# L1211_TOP_V2_0.net
KiCad netlist of a schematic drawn in Altium Designer
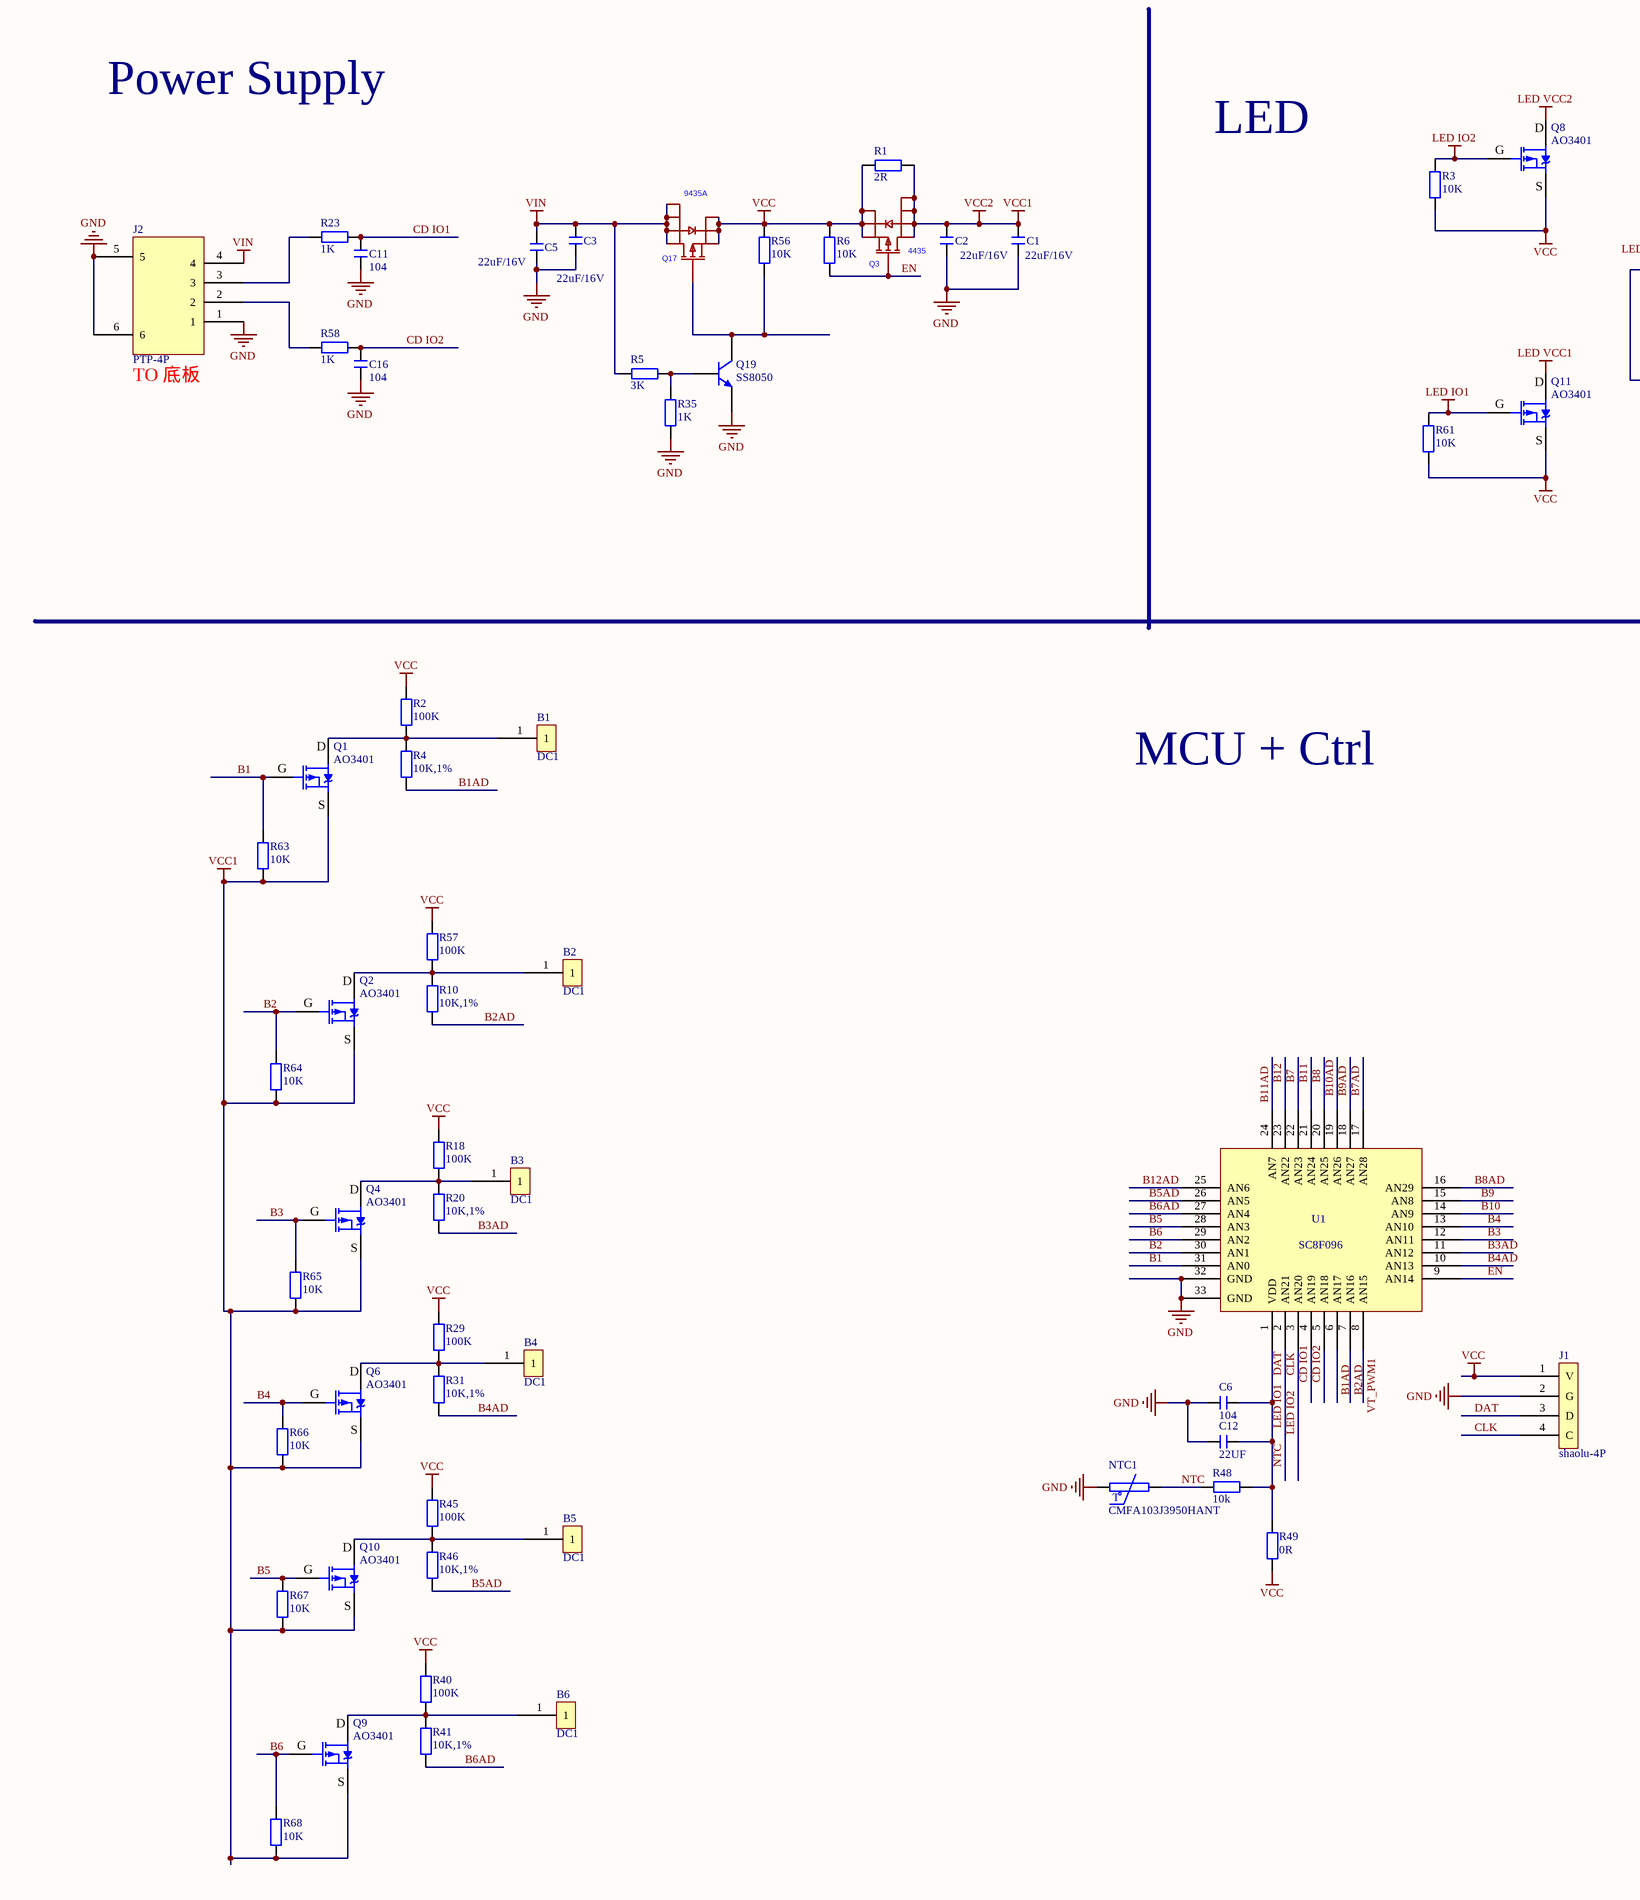
[diagram p0: L1211 TOP V2.0.SchDoc, left]
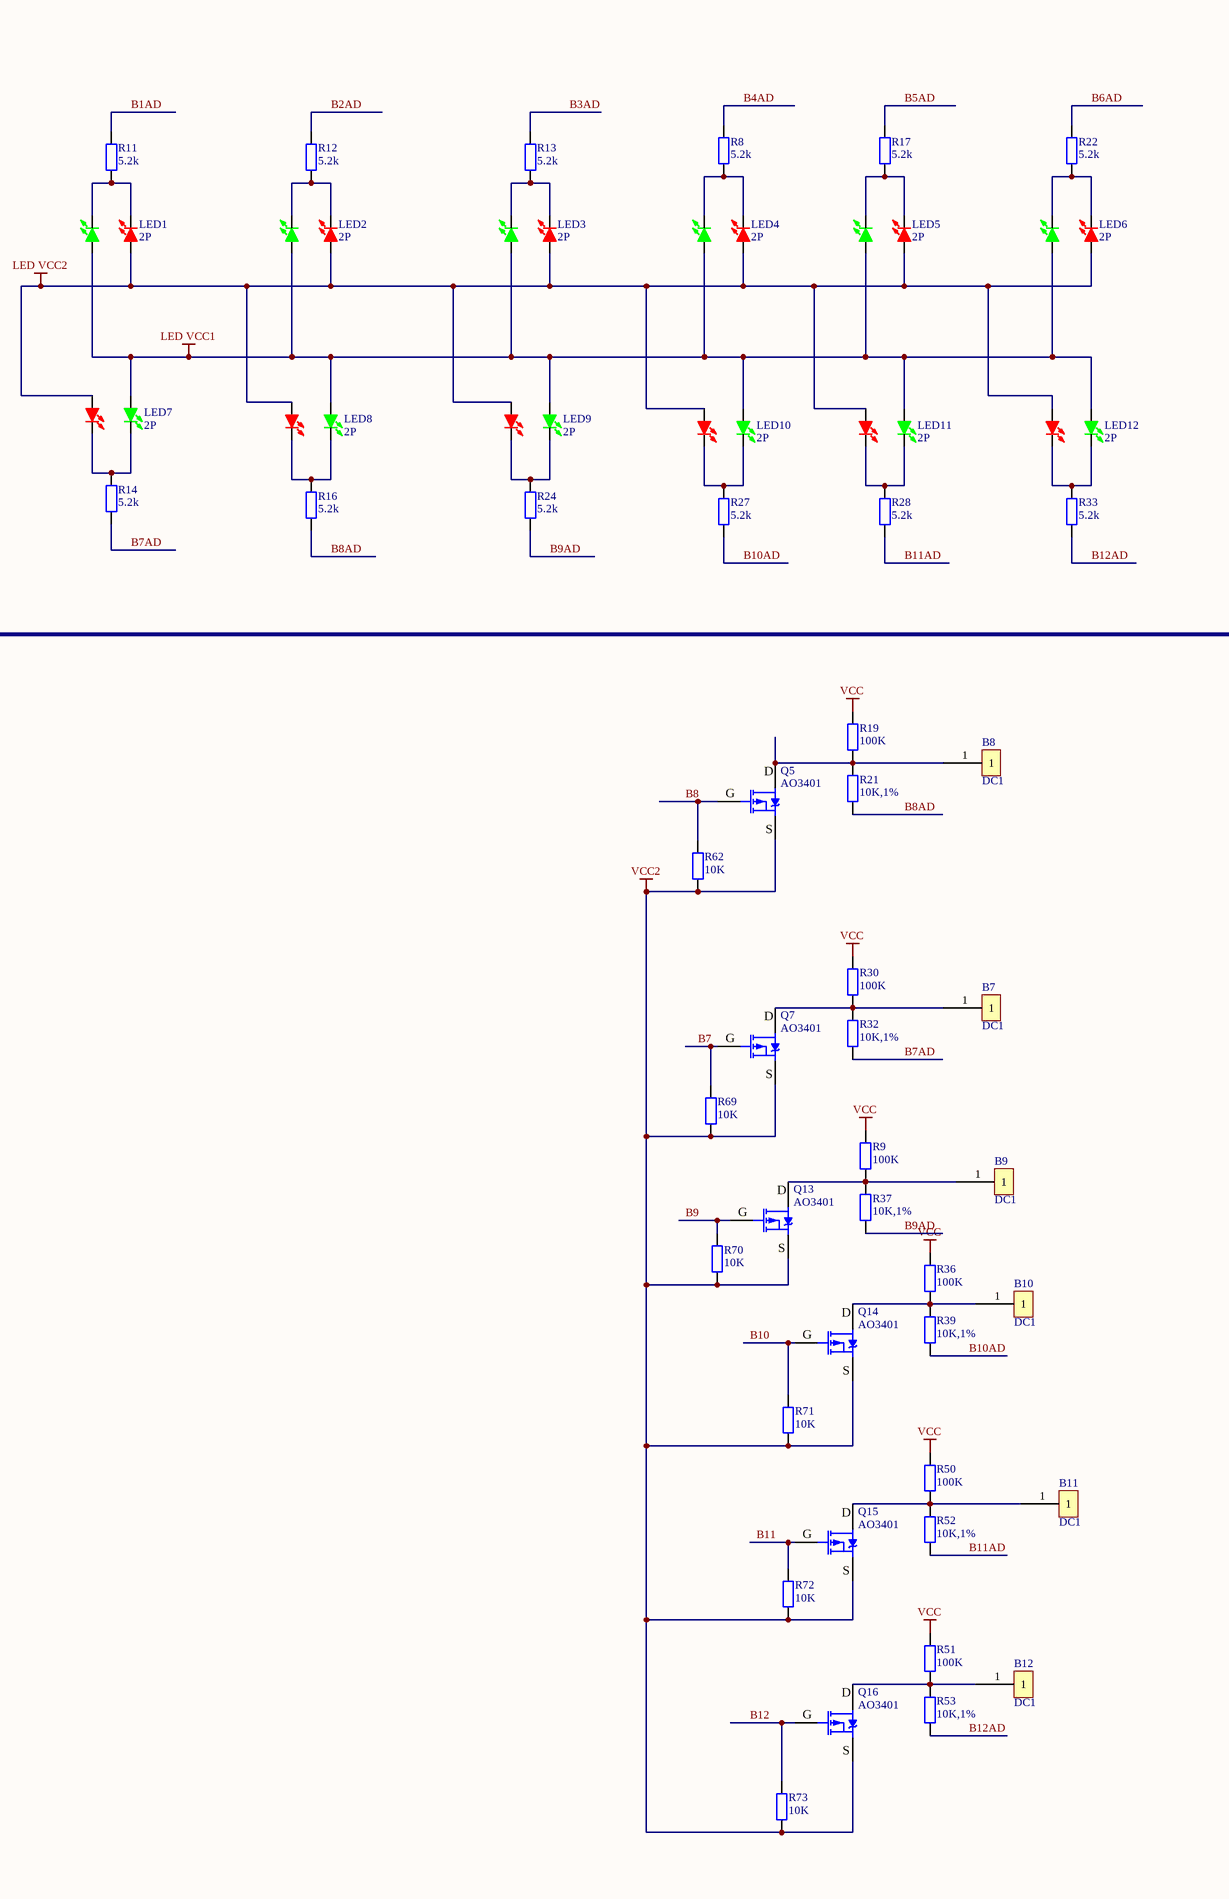
[diagram p1: L1211 TOP V2.0.SchDoc, right]

(export (version "E")
  (design (tool "Eeschema 10.0.6"))
  (components
    (comp (ref "B1") (value "DC1") (footprint "POPOPIN01") (libsource (lib "4.1   - 接口类") (part "dianchi1")))
    (comp (ref "B2") (value "DC1") (footprint "POPOPIN01") (libsource (lib "4.1   - 接口类") (part "dianchi1")))
    (comp (ref "B3") (value "DC1") (footprint "POPOPIN01") (libsource (lib "4.1   - 接口类") (part "dianchi1")))
    (comp (ref "B4") (value "DC1") (footprint "POPOPIN01") (libsource (lib "4.1   - 接口类") (part "dianchi1")))
    (comp (ref "B5") (value "DC1") (footprint "POPOPIN01") (libsource (lib "4.1   - 接口类") (part "dianchi1")))
    (comp (ref "B6") (value "DC1") (footprint "POPOPIN01") (libsource (lib "4.1   - 接口类") (part "dianchi1")))
    (comp (ref "B7") (value "DC1") (footprint "POPOPIN01") (libsource (lib "4.1   - 接口类") (part "dianchi1")))
    (comp (ref "B8") (value "DC1") (footprint "POPOPIN01") (libsource (lib "4.1   - 接口类") (part "dianchi1")))
    (comp (ref "B9") (value "DC1") (footprint "POPOPIN01") (libsource (lib "4.1   - 接口类") (part "dianchi1")))
    (comp (ref "B10") (value "DC1") (footprint "POPOPIN01") (libsource (lib "4.1   - 接口类") (part "dianchi1")))
    (comp (ref "B11") (value "DC1") (footprint "POPOPIN01") (libsource (lib "4.1   - 接口类") (part "dianchi1")))
    (comp (ref "B12") (value "DC1") (footprint "POPOPIN01") (libsource (lib "4.1   - 接口类") (part "dianchi1")))
    (comp (ref "C1")
      (value "22uF/16V")
      (footprint "0805L")
      (description "无极性贴片电容")
      (fields (field (name "版权归属") "源创客"))
      (libsource (lib "3.1   - 电阻-电容-电感") (part "C"))
    )
    (comp (ref "C2")
      (value "22uF/16V")
      (footprint "0805l")
      (description "无极性贴片电容")
      (fields (field (name "版权归属") "源创客"))
      (libsource (lib "3.1   - 电阻-电容-电感") (part "C"))
    )
    (comp (ref "C3")
      (value "22uF/16V")
      (footprint "0805l")
      (description "无极性贴片电容")
      (fields (field (name "版权归属") "源创客"))
      (libsource (lib "3.1   - 电阻-电容-电感") (part "C"))
    )
    (comp (ref "C5")
      (value "22uF/16V")
      (footprint "0805l")
      (description "无极性贴片电容")
      (fields (field (name "版权归属") "源创客"))
      (libsource (lib "3.1   - 电阻-电容-电感") (part "C"))
    )
    (comp (ref "C6")
      (value "104")
      (footprint "R0402")
      (description "无极性贴片电容")
      (fields (field (name "版权归属") "源创客"))
      (libsource (lib "3.1   - 电阻-电容-电感") (part "C"))
    )
    (comp (ref "C11")
      (value "104")
      (footprint "R0402")
      (description "无极性贴片电容")
      (fields (field (name "版权归属") "源创客"))
      (libsource (lib "3.1   - 电阻-电容-电感") (part "C"))
    )
    (comp (ref "C12")
      (value "22UF")
      (footprint "C 0603_L")
      (description "无极性贴片电容")
      (fields (field (name "版权归属") "源创客"))
      (libsource (lib "3.1   - 电阻-电容-电感") (part "C"))
    )
    (comp (ref "C16")
      (value "104")
      (footprint "R0402")
      (description "无极性贴片电容")
      (fields (field (name "版权归属") "源创客"))
      (libsource (lib "3.1   - 电阻-电容-电感") (part "C"))
    )
    (comp (ref "J1")
      (value "shaolu-4P")
      (footprint "shaolu-4P")
      (libsource (lib "4.1   - 接口类") (part "shaolu-4P"))
    )
    (comp (ref "J2") (value "PTP-4P") (footprint "PTP-4P") (libsource (lib "4.1   - 接口类") (part "PTP-4P")))
    (comp (ref "LED1")
      (value "2P")
      (footprint "LED 0606")
      (description "共阴双色LED")
      (fields (field (name "版权归属") "源创客"))
      (libsource (lib "9.1   - LED") (part "LED RG-K"))
    )
    (comp (ref "LED2")
      (value "2P")
      (footprint "LED 0606")
      (description "共阴双色LED")
      (fields (field (name "版权归属") "源创客"))
      (libsource (lib "9.1   - LED") (part "LED RG-K"))
    )
    (comp (ref "LED3")
      (value "2P")
      (footprint "LED 0606")
      (description "共阴双色LED")
      (fields (field (name "版权归属") "源创客"))
      (libsource (lib "9.1   - LED") (part "LED RG-K"))
    )
    (comp (ref "LED4")
      (value "2P")
      (footprint "LED 0606")
      (description "共阴双色LED")
      (fields (field (name "版权归属") "源创客"))
      (libsource (lib "9.1   - LED") (part "LED RG-K"))
    )
    (comp (ref "LED5")
      (value "2P")
      (footprint "LED 0606")
      (description "共阴双色LED")
      (fields (field (name "版权归属") "源创客"))
      (libsource (lib "9.1   - LED") (part "LED RG-K"))
    )
    (comp (ref "LED6")
      (value "2P")
      (footprint "LED 0606")
      (description "共阴双色LED")
      (fields (field (name "版权归属") "源创客"))
      (libsource (lib "9.1   - LED") (part "LED RG-K"))
    )
    (comp (ref "LED7")
      (value "2P")
      (footprint "LED 0606")
      (description "共阴双色LED")
      (fields (field (name "版权归属") "源创客"))
      (libsource (lib "9.1   - LED") (part "LED RG-K"))
    )
    (comp (ref "LED8")
      (value "2P")
      (footprint "LED 0606")
      (description "共阴双色LED")
      (fields (field (name "版权归属") "源创客"))
      (libsource (lib "9.1   - LED") (part "LED RG-K"))
    )
    (comp (ref "LED9")
      (value "2P")
      (footprint "LED 0606")
      (description "共阴双色LED")
      (fields (field (name "版权归属") "源创客"))
      (libsource (lib "9.1   - LED") (part "LED RG-K"))
    )
    (comp (ref "LED10")
      (value "2P")
      (footprint "LED 0606")
      (description "共阴双色LED")
      (fields (field (name "版权归属") "源创客"))
      (libsource (lib "9.1   - LED") (part "LED RG-K"))
    )
    (comp (ref "LED11")
      (value "2P")
      (footprint "LED 0606")
      (description "共阴双色LED")
      (fields (field (name "版权归属") "源创客"))
      (libsource (lib "9.1   - LED") (part "LED RG-K"))
    )
    (comp (ref "LED12")
      (value "2P")
      (footprint "LED 0606")
      (description "共阴双色LED")
      (fields (field (name "版权归属") "源创客"))
      (libsource (lib "9.1   - LED") (part "LED RG-K"))
    )
    (comp (ref "NTC1") (value "CMFA103J3950HANT") (footprint "0603L") (libsource (lib "*") (part "RES2-R")))
    (comp (ref "Q1")
      (value "AO3401")
      (footprint "SOT23-3N")
      (description "P沟道场效应管")
      (fields (field (name "版权归属") "源创客"))
      (libsource (lib "6.1   - 场效应管-可控硅") (part "SI2301"))
    )
    (comp (ref "Q2")
      (value "AO3401")
      (footprint "SOT23-3N")
      (description "P沟道场效应管")
      (fields (field (name "版权归属") "源创客"))
      (libsource (lib "6.1   - 场效应管-可控硅") (part "SI2301"))
    )
    (comp (ref "Q3")
      (value "4435")
      (footprint "SOP8_M")
      (fields (field (name "MANUFACTURER") "HL(富海微)") (field (name "MANUFACTURER PART") "9435A"))
      (libsource (lib "altium-import") (part "root_1_mirrored_9435A_"))
    )
    (comp (ref "Q4")
      (value "AO3401")
      (footprint "SOT23-3N")
      (description "P沟道场效应管")
      (fields (field (name "版权归属") "源创客"))
      (libsource (lib "6.1   - 场效应管-可控硅") (part "SI2301"))
    )
    (comp (ref "Q5")
      (value "AO3401")
      (footprint "SOT23-3N")
      (description "P沟道场效应管")
      (fields (field (name "版权归属") "源创客"))
      (libsource (lib "6.1   - 场效应管-可控硅") (part "SI2301"))
    )
    (comp (ref "Q6")
      (value "AO3401")
      (footprint "SOT23-3N")
      (description "P沟道场效应管")
      (fields (field (name "版权归属") "源创客"))
      (libsource (lib "6.1   - 场效应管-可控硅") (part "SI2301"))
    )
    (comp (ref "Q7")
      (value "AO3401")
      (footprint "SOT23-3N")
      (description "P沟道场效应管")
      (fields (field (name "版权归属") "源创客"))
      (libsource (lib "6.1   - 场效应管-可控硅") (part "SI2301"))
    )
    (comp (ref "Q8")
      (value "AO3401")
      (footprint "SOT23-3N")
      (description "P沟道场效应管")
      (fields (field (name "版权归属") "源创客"))
      (libsource (lib "6.1   - 场效应管-可控硅") (part "SI2301"))
    )
    (comp (ref "Q9")
      (value "AO3401")
      (footprint "SOT23-3N")
      (description "P沟道场效应管")
      (fields (field (name "版权归属") "源创客"))
      (libsource (lib "6.1   - 场效应管-可控硅") (part "SI2301"))
    )
    (comp (ref "Q10")
      (value "AO3401")
      (footprint "SOT23-3N")
      (description "P沟道场效应管")
      (fields (field (name "版权归属") "源创客"))
      (libsource (lib "6.1   - 场效应管-可控硅") (part "SI2301"))
    )
    (comp (ref "Q11")
      (value "AO3401")
      (footprint "SOT23-3N")
      (description "P沟道场效应管")
      (fields (field (name "版权归属") "源创客"))
      (libsource (lib "6.1   - 场效应管-可控硅") (part "SI2301"))
    )
    (comp (ref "Q13")
      (value "AO3401")
      (footprint "SOT23-3N")
      (description "P沟道场效应管")
      (fields (field (name "版权归属") "源创客"))
      (libsource (lib "6.1   - 场效应管-可控硅") (part "SI2301"))
    )
    (comp (ref "Q14")
      (value "AO3401")
      (footprint "SOT23-3N")
      (description "P沟道场效应管")
      (fields (field (name "版权归属") "源创客"))
      (libsource (lib "6.1   - 场效应管-可控硅") (part "SI2301"))
    )
    (comp (ref "Q15")
      (value "AO3401")
      (footprint "SOT23-3N")
      (description "P沟道场效应管")
      (fields (field (name "版权归属") "源创客"))
      (libsource (lib "6.1   - 场效应管-可控硅") (part "SI2301"))
    )
    (comp (ref "Q16")
      (value "AO3401")
      (footprint "SOT23-3N")
      (description "P沟道场效应管")
      (fields (field (name "版权归属") "源创客"))
      (libsource (lib "6.1   - 场效应管-可控硅") (part "SI2301"))
    )
    (comp (ref "Q17")
      (value "9435A")
      (footprint "SOP8")
      (fields (field (name "MANUFACTURER") "HL(富海微)"))
      (libsource (lib "altium-import") (part "root_1_9435A_"))
    )
    (comp (ref "Q19")
      (value "SS8050")
      (footprint "SOT23-3N")
      (description "NPN Bipolar Transistor")
      (fields (field (name "PUBLISHER") "Altium Limited"))
      (libsource (lib "Miscellaneous Devices") (part "QNPN"))
    )
    (comp (ref "R1")
      (value "2R")
      (footprint "R 1206_L")
      (description "贴片电阻")
      (fields (field (name "TOLERANCE") "±5%") (field (name "版权归属") "源创客"))
      (libsource (lib "3.1   - 电阻-电容-电感") (part "R"))
    )
    (comp (ref "R2")
      (value "100K")
      (footprint "R0402")
      (description "贴片电阻")
      (fields (field (name "TOLERANCE") "±5%") (field (name "版权归属") "源创客"))
      (libsource (lib "3.1   - 电阻-电容-电感") (part "R"))
    )
    (comp (ref "R3")
      (value "10K")
      (footprint "R0402")
      (description "贴片电阻")
      (fields
        (field (name "TOLERANCE") "±5%")
        (field (name "TOLERANCE_1") "Tolerance")
        (field (name "版权归属") "源创客")
      )
      (libsource (lib "3.1   - 电阻-电容-电感") (part "R"))
    )
    (comp (ref "R4")
      (value "10K,1%")
      (footprint "R0402")
      (description "贴片电阻")
      (fields (field (name "TOLERANCE") "±1%"))
      (libsource (lib "3.1   - 电阻-电容-电感") (part "R"))
    )
    (comp (ref "R5")
      (value "3K")
      (footprint "R0402")
      (description "贴片电阻")
      (fields (field (name "版权归属") "源创客"))
      (libsource (lib "3.1   - 电阻-电容-电感") (part "R"))
    )
    (comp (ref "R6")
      (value "10K")
      (footprint "R0402")
      (description "贴片电阻")
      (fields (field (name "TOLERANCE") "±5%") (field (name "版权归属") "源创客"))
      (libsource (lib "3.1   - 电阻-电容-电感") (part "R"))
    )
    (comp (ref "R8")
      (value "5.2k")
      (footprint "R0402")
      (description "贴片电阻")
      (fields
        (field (name "TOLERANCE") "±5%")
        (field (name "TOLERANCE_1") "Tolerance")
        (field (name "版权归属") "源创客")
      )
      (libsource (lib "3.1   - 电阻-电容-电感") (part "R"))
    )
    (comp (ref "R9")
      (value "100K")
      (footprint "R0402")
      (description "贴片电阻")
      (fields (field (name "TOLERANCE") "±5%") (field (name "版权归属") "源创客"))
      (libsource (lib "3.1   - 电阻-电容-电感") (part "R"))
    )
    (comp (ref "R10")
      (value "10K,1%")
      (footprint "R0402")
      (description "贴片电阻")
      (fields (field (name "TOLERANCE") "±1%"))
      (libsource (lib "3.1   - 电阻-电容-电感") (part "R"))
    )
    (comp (ref "R11")
      (value "5.2k")
      (footprint "R0402")
      (description "贴片电阻")
      (fields
        (field (name "TOLERANCE") "±5%")
        (field (name "TOLERANCE_1") "Tolerance")
        (field (name "版权归属") "源创客")
      )
      (libsource (lib "3.1   - 电阻-电容-电感") (part "R"))
    )
    (comp (ref "R12")
      (value "5.2k")
      (footprint "R0402")
      (description "贴片电阻")
      (fields
        (field (name "TOLERANCE") "±5%")
        (field (name "TOLERANCE_1") "Tolerance")
        (field (name "版权归属") "源创客")
      )
      (libsource (lib "3.1   - 电阻-电容-电感") (part "R"))
    )
    (comp (ref "R13")
      (value "5.2k")
      (footprint "R0402")
      (description "贴片电阻")
      (fields
        (field (name "TOLERANCE") "±5%")
        (field (name "TOLERANCE_1") "Tolerance")
        (field (name "版权归属") "源创客")
      )
      (libsource (lib "3.1   - 电阻-电容-电感") (part "R"))
    )
    (comp (ref "R14")
      (value "5.2k")
      (footprint "R0402")
      (description "贴片电阻")
      (fields
        (field (name "TOLERANCE") "±5%")
        (field (name "TOLERANCE_1") "Tolerance")
        (field (name "版权归属") "源创客")
      )
      (libsource (lib "3.1   - 电阻-电容-电感") (part "R"))
    )
    (comp (ref "R16")
      (value "5.2k")
      (footprint "R0402")
      (description "贴片电阻")
      (fields
        (field (name "TOLERANCE") "±5%")
        (field (name "TOLERANCE_1") "Tolerance")
        (field (name "版权归属") "源创客")
      )
      (libsource (lib "3.1   - 电阻-电容-电感") (part "R"))
    )
    (comp (ref "R17")
      (value "5.2k")
      (footprint "R0402")
      (description "贴片电阻")
      (fields
        (field (name "TOLERANCE") "±5%")
        (field (name "TOLERANCE_1") "Tolerance")
        (field (name "版权归属") "源创客")
      )
      (libsource (lib "3.1   - 电阻-电容-电感") (part "R"))
    )
    (comp (ref "R18")
      (value "100K")
      (footprint "R0402")
      (description "贴片电阻")
      (fields
        (field (name "TOLERANCE") "Tolerance")
        (field (name "TOLERANCE_1") "±5%")
        (field (name "版权归属") "源创客")
      )
      (libsource (lib "3.1   - 电阻-电容-电感") (part "R"))
    )
    (comp (ref "R19")
      (value "100K")
      (footprint "R0402")
      (description "贴片电阻")
      (fields (field (name "TOLERANCE") "±5%") (field (name "版权归属") "源创客"))
      (libsource (lib "3.1   - 电阻-电容-电感") (part "R"))
    )
    (comp (ref "R20")
      (value "10K,1%")
      (footprint "R0402")
      (description "贴片电阻")
      (fields (field (name "TOLERANCE") "±1%"))
      (libsource (lib "3.1   - 电阻-电容-电感") (part "R"))
    )
    (comp (ref "R21")
      (value "10K,1%")
      (footprint "R0402")
      (description "贴片电阻")
      (fields (field (name "TOLERANCE") "±1%"))
      (libsource (lib "3.1   - 电阻-电容-电感") (part "R"))
    )
    (comp (ref "R22")
      (value "5.2k")
      (footprint "R0402")
      (description "贴片电阻")
      (fields
        (field (name "TOLERANCE") "±5%")
        (field (name "TOLERANCE_1") "Tolerance")
        (field (name "版权归属") "源创客")
      )
      (libsource (lib "3.1   - 电阻-电容-电感") (part "R"))
    )
    (comp (ref "R23")
      (value "1K")
      (footprint "R0402")
      (description "贴片电阻")
      (fields (field (name "版权归属") "源创客"))
      (libsource (lib "3.1   - 电阻-电容-电感") (part "R"))
    )
    (comp (ref "R24")
      (value "5.2k")
      (footprint "R0402")
      (description "贴片电阻")
      (fields
        (field (name "TOLERANCE") "±5%")
        (field (name "TOLERANCE_1") "Tolerance")
        (field (name "版权归属") "源创客")
      )
      (libsource (lib "3.1   - 电阻-电容-电感") (part "R"))
    )
    (comp (ref "R27")
      (value "5.2k")
      (footprint "R0402")
      (description "贴片电阻")
      (fields
        (field (name "TOLERANCE") "±5%")
        (field (name "TOLERANCE_1") "Tolerance")
        (field (name "版权归属") "源创客")
      )
      (libsource (lib "3.1   - 电阻-电容-电感") (part "R"))
    )
    (comp (ref "R28")
      (value "5.2k")
      (footprint "R0402")
      (description "贴片电阻")
      (fields
        (field (name "TOLERANCE") "±5%")
        (field (name "TOLERANCE_1") "Tolerance")
        (field (name "版权归属") "源创客")
      )
      (libsource (lib "3.1   - 电阻-电容-电感") (part "R"))
    )
    (comp (ref "R29")
      (value "100K")
      (footprint "R0402")
      (description "贴片电阻")
      (fields (field (name "TOLERANCE") "±5%"))
      (libsource (lib "3.1   - 电阻-电容-电感") (part "R"))
    )
    (comp (ref "R30")
      (value "100K")
      (footprint "R0402")
      (description "贴片电阻")
      (fields (field (name "TOLERANCE") "±5%") (field (name "版权归属") "源创客"))
      (libsource (lib "3.1   - 电阻-电容-电感") (part "R"))
    )
    (comp (ref "R31")
      (value "10K,1%")
      (footprint "R0402")
      (description "贴片电阻")
      (fields (field (name "TOLERANCE") "±1%"))
      (libsource (lib "3.1   - 电阻-电容-电感") (part "R"))
    )
    (comp (ref "R32")
      (value "10K,1%")
      (footprint "R0402")
      (description "贴片电阻")
      (fields (field (name "TOLERANCE") "±1%"))
      (libsource (lib "3.1   - 电阻-电容-电感") (part "R"))
    )
    (comp (ref "R33")
      (value "5.2k")
      (footprint "R0402")
      (description "贴片电阻")
      (fields
        (field (name "TOLERANCE") "±5%")
        (field (name "TOLERANCE_1") "Tolerance")
        (field (name "版权归属") "源创客")
      )
      (libsource (lib "3.1   - 电阻-电容-电感") (part "R"))
    )
    (comp (ref "R35")
      (value "1K")
      (footprint "R0402")
      (description "贴片电阻")
      (fields (field (name "版权归属") "源创客"))
      (libsource (lib "3.1   - 电阻-电容-电感") (part "R"))
    )
    (comp (ref "R36")
      (value "100K")
      (footprint "R0402")
      (description "贴片电阻")
      (fields (field (name "TOLERANCE") "±5%"))
      (libsource (lib "3.1   - 电阻-电容-电感") (part "R"))
    )
    (comp (ref "R37")
      (value "10K,1%")
      (footprint "R0402")
      (description "贴片电阻")
      (fields (field (name "TOLERANCE") "±1%"))
      (libsource (lib "3.1   - 电阻-电容-电感") (part "R"))
    )
    (comp (ref "R39")
      (value "10K,1%")
      (footprint "R0402")
      (description "贴片电阻")
      (fields (field (name "TOLERANCE") "±1%"))
      (libsource (lib "3.1   - 电阻-电容-电感") (part "R"))
    )
    (comp (ref "R40")
      (value "100K")
      (footprint "R0402")
      (description "贴片电阻")
      (fields (field (name "TOLERANCE") "±5%") (field (name "版权归属") "源创客"))
      (libsource (lib "3.1   - 电阻-电容-电感") (part "R"))
    )
    (comp (ref "R41")
      (value "10K,1%")
      (footprint "R0402")
      (description "贴片电阻")
      (fields (field (name "TOLERANCE") "±1%"))
      (libsource (lib "3.1   - 电阻-电容-电感") (part "R"))
    )
    (comp (ref "R45")
      (value "100K")
      (footprint "R0402")
      (description "贴片电阻")
      (fields (field (name "TOLERANCE") "±5%") (field (name "版权归属") "源创客"))
      (libsource (lib "3.1   - 电阻-电容-电感") (part "R"))
    )
    (comp (ref "R46")
      (value "10K,1%")
      (footprint "R0402")
      (description "贴片电阻")
      (fields (field (name "TOLERANCE") "±1%"))
      (libsource (lib "3.1   - 电阻-电容-电感") (part "R"))
    )
    (comp (ref "R48")
      (value "10k")
      (footprint "R0402")
      (description "贴片电阻")
      (fields
        (field (name "TOLERANCE") "Tolerance")
        (field (name "TOLERANCE_1") "±5%")
        (field (name "版权归属") "源创客")
      )
      (libsource (lib "3.1   - 电阻-电容-电感") (part "R"))
    )
    (comp (ref "R49")
      (value "0R")
      (footprint "R0402")
      (description "贴片电阻")
      (fields
        (field (name "TOLERANCE") "Tolerance")
        (field (name "TOLERANCE_1") "±5%")
        (field (name "版权归属") "源创客")
      )
      (libsource (lib "3.1   - 电阻-电容-电感") (part "R"))
    )
    (comp (ref "R50")
      (value "100K")
      (footprint "R0402")
      (description "贴片电阻")
      (fields (field (name "TOLERANCE") "±5%") (field (name "版权归属") "源创客"))
      (libsource (lib "3.1   - 电阻-电容-电感") (part "R"))
    )
    (comp (ref "R51")
      (value "100K")
      (footprint "R0402")
      (description "贴片电阻")
      (fields (field (name "TOLERANCE") "±5%"))
      (libsource (lib "3.1   - 电阻-电容-电感") (part "R"))
    )
    (comp (ref "R52")
      (value "10K,1%")
      (footprint "R0402")
      (description "贴片电阻")
      (fields (field (name "TOLERANCE") "±1%"))
      (libsource (lib "3.1   - 电阻-电容-电感") (part "R"))
    )
    (comp (ref "R53")
      (value "10K,1%")
      (footprint "R0402")
      (description "贴片电阻")
      (fields (field (name "TOLERANCE") "±1%"))
      (libsource (lib "3.1   - 电阻-电容-电感") (part "R"))
    )
    (comp (ref "R56")
      (value "10K")
      (footprint "R0402")
      (description "贴片电阻")
      (fields (field (name "TOLERANCE") "±5%") (field (name "版权归属") "源创客"))
      (libsource (lib "3.1   - 电阻-电容-电感") (part "R"))
    )
    (comp (ref "R57")
      (value "100K")
      (footprint "R0402")
      (description "贴片电阻")
      (fields
        (field (name "TOLERANCE") "Tolerance")
        (field (name "TOLERANCE_1") "±5%")
        (field (name "版权归属") "源创客")
      )
      (libsource (lib "3.1   - 电阻-电容-电感") (part "R"))
    )
    (comp (ref "R58")
      (value "1K")
      (footprint "R0402")
      (description "贴片电阻")
      (fields (field (name "版权归属") "源创客"))
      (libsource (lib "3.1   - 电阻-电容-电感") (part "R"))
    )
    (comp (ref "R61")
      (value "10K")
      (footprint "R0402")
      (description "贴片电阻")
      (fields
        (field (name "TOLERANCE") "±5%")
        (field (name "TOLERANCE_1") "Tolerance")
        (field (name "版权归属") "源创客")
      )
      (libsource (lib "3.1   - 电阻-电容-电感") (part "R"))
    )
    (comp (ref "R62")
      (value "10K")
      (footprint "R0402")
      (description "贴片电阻")
      (fields (field (name "TOLERANCE") "±5%") (field (name "版权归属") "源创客"))
      (libsource (lib "3.1   - 电阻-电容-电感") (part "R"))
    )
    (comp (ref "R63")
      (value "10K")
      (footprint "R0402")
      (description "贴片电阻")
      (fields (field (name "TOLERANCE") "±5%") (field (name "版权归属") "源创客"))
      (libsource (lib "3.1   - 电阻-电容-电感") (part "R"))
    )
    (comp (ref "R64")
      (value "10K")
      (footprint "R0402")
      (description "贴片电阻")
      (fields (field (name "TOLERANCE") "±5%") (field (name "版权归属") "源创客"))
      (libsource (lib "3.1   - 电阻-电容-电感") (part "R"))
    )
    (comp (ref "R65")
      (value "10K")
      (footprint "R0402")
      (description "贴片电阻")
      (fields (field (name "TOLERANCE") "±5%") (field (name "版权归属") "源创客"))
      (libsource (lib "3.1   - 电阻-电容-电感") (part "R"))
    )
    (comp (ref "R66")
      (value "10K")
      (footprint "R0402")
      (description "贴片电阻")
      (fields (field (name "TOLERANCE") "±5%") (field (name "版权归属") "源创客"))
      (libsource (lib "3.1   - 电阻-电容-电感") (part "R"))
    )
    (comp (ref "R67")
      (value "10K")
      (footprint "R0402")
      (description "贴片电阻")
      (fields (field (name "TOLERANCE") "±5%") (field (name "版权归属") "源创客"))
      (libsource (lib "3.1   - 电阻-电容-电感") (part "R"))
    )
    (comp (ref "R68")
      (value "10K")
      (footprint "R0402")
      (description "贴片电阻")
      (fields (field (name "TOLERANCE") "±5%") (field (name "版权归属") "源创客"))
      (libsource (lib "3.1   - 电阻-电容-电感") (part "R"))
    )
    (comp (ref "R69")
      (value "10K")
      (footprint "R0402")
      (description "贴片电阻")
      (fields (field (name "TOLERANCE") "±5%") (field (name "版权归属") "源创客"))
      (libsource (lib "3.1   - 电阻-电容-电感") (part "R"))
    )
    (comp (ref "R70")
      (value "10K")
      (footprint "R0402")
      (description "贴片电阻")
      (fields (field (name "TOLERANCE") "±5%") (field (name "版权归属") "源创客"))
      (libsource (lib "3.1   - 电阻-电容-电感") (part "R"))
    )
    (comp (ref "R71")
      (value "10K")
      (footprint "R0402")
      (description "贴片电阻")
      (fields (field (name "TOLERANCE") "±5%") (field (name "版权归属") "源创客"))
      (libsource (lib "3.1   - 电阻-电容-电感") (part "R"))
    )
    (comp (ref "R72")
      (value "10K")
      (footprint "R0402")
      (description "贴片电阻")
      (fields (field (name "TOLERANCE") "±5%") (field (name "版权归属") "源创客"))
      (libsource (lib "3.1   - 电阻-电容-电感") (part "R"))
    )
    (comp (ref "R73")
      (value "10K")
      (footprint "R0402")
      (description "贴片电阻")
      (fields (field (name "TOLERANCE") "±5%") (field (name "版权归属") "源创客"))
      (libsource (lib "3.1   - 电阻-电容-电感") (part "R"))
    )
    (comp (ref "U1")
      (value "SC8F096")
      (footprint "QFN-32-4*4")
      (libsource (lib "1.1   - IC芯片") (part "SC8F096AD832NPR"))
    )
  )
  (nets
    (net (code "1") (name "/B1") (class "Default")
      (node (ref "Q1") (pin "1") (pinfunction "G_1") (pintype "passive"))
      (node (ref "R63") (pin "2") (pinfunction "2_2") (pintype "passive"))
      (node (ref "U1") (pin "31") (pinfunction "AN0_31") (pintype "passive"))
    )
    (net (code "2") (name "/B1AD") (class "Default")
      (node (ref "R11") (pin "2") (pinfunction "2_2") (pintype "passive"))
      (node (ref "R4") (pin "1") (pinfunction "1_1") (pintype "passive"))
      (node (ref "U1") (pin "6") (pinfunction "AN17_6") (pintype "passive"))
    )
    (net (code "3") (name "/B2") (class "Default")
      (node (ref "Q2") (pin "1") (pinfunction "G_1") (pintype "passive"))
      (node (ref "R64") (pin "2") (pinfunction "2_2") (pintype "passive"))
      (node (ref "U1") (pin "30") (pinfunction "AN1_30") (pintype "passive"))
    )
    (net (code "4") (name "/B2AD") (class "Default")
      (node (ref "R10") (pin "1") (pinfunction "1_1") (pintype "passive"))
      (node (ref "R12") (pin "2") (pinfunction "2_2") (pintype "passive"))
      (node (ref "U1") (pin "7") (pinfunction "AN16_7") (pintype "passive"))
    )
    (net (code "5") (name "/B3") (class "Default")
      (node (ref "Q4") (pin "1") (pinfunction "G_1") (pintype "passive"))
      (node (ref "R65") (pin "2") (pinfunction "2_2") (pintype "passive"))
      (node (ref "U1") (pin "12") (pinfunction "AN11_12") (pintype "passive"))
    )
    (net (code "6") (name "/B3AD") (class "Default")
      (node (ref "R13") (pin "2") (pinfunction "2_2") (pintype "passive"))
      (node (ref "R20") (pin "1") (pinfunction "1_1") (pintype "passive"))
      (node (ref "U1") (pin "11") (pinfunction "AN12_11") (pintype "passive"))
    )
    (net (code "7") (name "/B4") (class "Default")
      (node (ref "Q6") (pin "1") (pinfunction "G_1") (pintype "passive"))
      (node (ref "R66") (pin "2") (pinfunction "2_2") (pintype "passive"))
      (node (ref "U1") (pin "13") (pinfunction "AN10_13") (pintype "passive"))
    )
    (net (code "8") (name "/B4AD") (class "Default")
      (node (ref "R31") (pin "1") (pinfunction "1_1") (pintype "passive"))
      (node (ref "R8") (pin "2") (pinfunction "2_2") (pintype "passive"))
      (node (ref "U1") (pin "10") (pinfunction "AN13_10") (pintype "passive"))
    )
    (net (code "9") (name "/B5") (class "Default")
      (node (ref "Q10") (pin "1") (pinfunction "G_1") (pintype "passive"))
      (node (ref "R67") (pin "2") (pinfunction "2_2") (pintype "passive"))
      (node (ref "U1") (pin "28") (pinfunction "AN3_28") (pintype "passive"))
    )
    (net (code "10") (name "/B5AD") (class "Default")
      (node (ref "R17") (pin "2") (pinfunction "2_2") (pintype "passive"))
      (node (ref "R46") (pin "1") (pinfunction "1_1") (pintype "passive"))
      (node (ref "U1") (pin "26") (pinfunction "AN5_26") (pintype "passive"))
    )
    (net (code "11") (name "/B6") (class "Default")
      (node (ref "Q9") (pin "1") (pinfunction "G_1") (pintype "passive"))
      (node (ref "R68") (pin "2") (pinfunction "2_2") (pintype "passive"))
      (node (ref "U1") (pin "29") (pinfunction "AN2_29") (pintype "passive"))
    )
    (net (code "12") (name "/B6AD") (class "Default")
      (node (ref "R22") (pin "2") (pinfunction "2_2") (pintype "passive"))
      (node (ref "R41") (pin "1") (pinfunction "1_1") (pintype "passive"))
      (node (ref "U1") (pin "27") (pinfunction "AN4_27") (pintype "passive"))
    )
    (net (code "13") (name "/B7") (class "Default")
      (node (ref "Q7") (pin "1") (pinfunction "G_1") (pintype "passive"))
      (node (ref "R69") (pin "2") (pinfunction "2_2") (pintype "passive"))
      (node (ref "U1") (pin "22") (pinfunction "AN23_22") (pintype "passive"))
    )
    (net (code "14") (name "/B7AD") (class "Default")
      (node (ref "R14") (pin "1") (pinfunction "1_1") (pintype "passive"))
      (node (ref "R32") (pin "1") (pinfunction "1_1") (pintype "passive"))
      (node (ref "U1") (pin "17") (pinfunction "AN28_17") (pintype "passive"))
    )
    (net (code "15") (name "/B8") (class "Default")
      (node (ref "Q5") (pin "1") (pinfunction "G_1") (pintype "passive"))
      (node (ref "R62") (pin "2") (pinfunction "2_2") (pintype "passive"))
      (node (ref "U1") (pin "20") (pinfunction "AN25_20") (pintype "passive"))
    )
    (net (code "16") (name "/B8AD") (class "Default")
      (node (ref "R16") (pin "1") (pinfunction "1_1") (pintype "passive"))
      (node (ref "R21") (pin "1") (pinfunction "1_1") (pintype "passive"))
      (node (ref "U1") (pin "16") (pinfunction "AN29_16") (pintype "passive"))
    )
    (net (code "17") (name "/B9") (class "Default")
      (node (ref "Q13") (pin "1") (pinfunction "G_1") (pintype "passive"))
      (node (ref "R70") (pin "2") (pinfunction "2_2") (pintype "passive"))
      (node (ref "U1") (pin "15") (pinfunction "AN8_15") (pintype "passive"))
    )
    (net (code "18") (name "/B9AD") (class "Default")
      (node (ref "R24") (pin "1") (pinfunction "1_1") (pintype "passive"))
      (node (ref "R37") (pin "1") (pinfunction "1_1") (pintype "passive"))
      (node (ref "U1") (pin "18") (pinfunction "AN27_18") (pintype "passive"))
    )
    (net (code "19") (name "/B10") (class "Default")
      (node (ref "Q14") (pin "1") (pinfunction "G_1") (pintype "passive"))
      (node (ref "R71") (pin "2") (pinfunction "2_2") (pintype "passive"))
      (node (ref "U1") (pin "14") (pinfunction "AN9_14") (pintype "passive"))
    )
    (net (code "20") (name "/B10AD") (class "Default")
      (node (ref "R27") (pin "1") (pinfunction "1_1") (pintype "passive"))
      (node (ref "R39") (pin "1") (pinfunction "1_1") (pintype "passive"))
      (node (ref "U1") (pin "19") (pinfunction "AN26_19") (pintype "passive"))
    )
    (net (code "21") (name "/B11") (class "Default")
      (node (ref "Q15") (pin "1") (pinfunction "G_1") (pintype "passive"))
      (node (ref "R72") (pin "2") (pinfunction "2_2") (pintype "passive"))
      (node (ref "U1") (pin "21") (pinfunction "AN24_21") (pintype "passive"))
    )
    (net (code "22") (name "/B11AD") (class "Default")
      (node (ref "R28") (pin "1") (pinfunction "1_1") (pintype "passive"))
      (node (ref "R52") (pin "1") (pinfunction "1_1") (pintype "passive"))
      (node (ref "U1") (pin "24") (pinfunction "AN7_24") (pintype "passive"))
    )
    (net (code "23") (name "/B12") (class "Default")
      (node (ref "Q16") (pin "1") (pinfunction "G_1") (pintype "passive"))
      (node (ref "R73") (pin "2") (pinfunction "2_2") (pintype "passive"))
      (node (ref "U1") (pin "23") (pinfunction "AN22_23") (pintype "passive"))
    )
    (net (code "24") (name "/B12AD") (class "Default")
      (node (ref "R33") (pin "1") (pinfunction "1_1") (pintype "passive"))
      (node (ref "R53") (pin "1") (pinfunction "1_1") (pintype "passive"))
      (node (ref "U1") (pin "25") (pinfunction "AN6_25") (pintype "passive"))
    )
    (net (code "25") (name "/CD IO1") (class "Default")
      (node (ref "C11") (pin "2") (pinfunction "2_2") (pintype "passive"))
      (node (ref "R23") (pin "2") (pinfunction "2_2") (pintype "passive"))
      (node (ref "U1") (pin "4") (pinfunction "AN19_4") (pintype "passive"))
    )
    (net (code "26") (name "/CD IO2") (class "Default")
      (node (ref "C16") (pin "2") (pinfunction "2_2") (pintype "passive"))
      (node (ref "R58") (pin "2") (pinfunction "2_2") (pintype "passive"))
      (node (ref "U1") (pin "5") (pinfunction "AN18_5") (pintype "passive"))
    )
    (net (code "27") (name "/EN") (class "Default")
      (node (ref "Q3") (pin "4") (pinfunction "G_4") (pintype "passive"))
      (node (ref "R6") (pin "1") (pinfunction "1_1") (pintype "passive"))
      (node (ref "U1") (pin "9") (pinfunction "AN14_9") (pintype "passive"))
    )
    (net (code "28") (name "/VT_PWM1") (class "Default")
      (node (ref "U1") (pin "8") (pinfunction "AN15_8") (pintype "passive"))
    )
    (net (code "29") (name "GND") (class "Default")
      (node (ref "C1") (pin "1") (pinfunction "1_1") (pintype "passive"))
      (node (ref "C11") (pin "1") (pinfunction "1_1") (pintype "passive"))
      (node (ref "C12") (pin "1") (pinfunction "1_1") (pintype "passive"))
      (node (ref "C16") (pin "1") (pinfunction "1_1") (pintype "passive"))
      (node (ref "C2") (pin "1") (pinfunction "1_1") (pintype "passive"))
      (node (ref "C3") (pin "1") (pinfunction "1_1") (pintype "passive"))
      (node (ref "C5") (pin "1") (pinfunction "1_1") (pintype "passive"))
      (node (ref "C6") (pin "1") (pinfunction "1_1") (pintype "passive"))
      (node (ref "J1") (pin "2") (pinfunction "G_2") (pintype "passive"))
      (node (ref "J2") (pin "1") (pinfunction "1_1") (pintype "passive"))
      (node (ref "J2") (pin "5") (pinfunction "5_5") (pintype "passive"))
      (node (ref "J2") (pin "6") (pinfunction "6_6") (pintype "passive"))
      (node (ref "NTC1") (pin "1") (pinfunction "1_1") (pintype "passive"))
      (node (ref "Q19") (pin "2") (pinfunction "E_2") (pintype "passive"))
      (node (ref "R35") (pin "1") (pinfunction "1_1") (pintype "passive"))
      (node (ref "U1") (pin "32") (pinfunction "GND_32") (pintype "passive"))
      (node (ref "U1") (pin "33") (pinfunction "GND_33") (pintype "passive"))
    )
    (net (code "30") (name "LED IO1") (class "Default")
      (node (ref "J1") (pin "3") (pinfunction "D_3") (pintype "passive"))
      (node (ref "NTC1") (pin "2") (pinfunction "2_2") (pintype "passive"))
      (node (ref "Q11") (pin "1") (pinfunction "G_1") (pintype "passive"))
      (node (ref "R48") (pin "2") (pinfunction "2_2") (pintype "passive"))
      (node (ref "R61") (pin "2") (pinfunction "2_2") (pintype "passive"))
      (node (ref "U1") (pin "2") (pinfunction "AN21_2") (pintype "passive"))
    )
    (net (code "31") (name "LED IO2") (class "Default")
      (node (ref "J1") (pin "4") (pinfunction "C_4") (pintype "passive"))
      (node (ref "Q8") (pin "1") (pinfunction "G_1") (pintype "passive"))
      (node (ref "R3") (pin "2") (pinfunction "2_2") (pintype "passive"))
      (node (ref "U1") (pin "3") (pinfunction "AN20_3") (pintype "passive"))
    )
    (net (code "32") (name "LED VCC1") (class "Default")
      (node (ref "LED1") (pin "3") (pinfunction "3_3") (pintype "passive"))
      (node (ref "LED10") (pin "3") (pinfunction "3_3") (pintype "passive"))
      (node (ref "LED11") (pin "3") (pinfunction "3_3") (pintype "passive"))
      (node (ref "LED12") (pin "3") (pinfunction "3_3") (pintype "passive"))
      (node (ref "LED2") (pin "3") (pinfunction "3_3") (pintype "passive"))
      (node (ref "LED3") (pin "3") (pinfunction "3_3") (pintype "passive"))
      (node (ref "LED4") (pin "3") (pinfunction "3_3") (pintype "passive"))
      (node (ref "LED5") (pin "3") (pinfunction "3_3") (pintype "passive"))
      (node (ref "LED6") (pin "3") (pinfunction "3_3") (pintype "passive"))
      (node (ref "LED7") (pin "3") (pinfunction "3_3") (pintype "passive"))
      (node (ref "LED8") (pin "3") (pinfunction "3_3") (pintype "passive"))
      (node (ref "LED9") (pin "3") (pinfunction "3_3") (pintype "passive"))
      (node (ref "Q11") (pin "3") (pinfunction "D_3") (pintype "passive"))
    )
    (net (code "33") (name "LED VCC2") (class "Default")
      (node (ref "LED1") (pin "1") (pinfunction "1_1") (pintype "passive"))
      (node (ref "LED10") (pin "1") (pinfunction "1_1") (pintype "passive"))
      (node (ref "LED11") (pin "1") (pinfunction "1_1") (pintype "passive"))
      (node (ref "LED12") (pin "1") (pinfunction "1_1") (pintype "passive"))
      (node (ref "LED2") (pin "1") (pinfunction "1_1") (pintype "passive"))
      (node (ref "LED3") (pin "1") (pinfunction "1_1") (pintype "passive"))
      (node (ref "LED4") (pin "1") (pinfunction "1_1") (pintype "passive"))
      (node (ref "LED5") (pin "1") (pinfunction "1_1") (pintype "passive"))
      (node (ref "LED6") (pin "1") (pinfunction "1_1") (pintype "passive"))
      (node (ref "LED7") (pin "1") (pinfunction "1_1") (pintype "passive"))
      (node (ref "LED8") (pin "1") (pinfunction "1_1") (pintype "passive"))
      (node (ref "LED9") (pin "1") (pinfunction "1_1") (pintype "passive"))
      (node (ref "Q8") (pin "3") (pinfunction "D_3") (pintype "passive"))
    )
    (net (code "34") (name "Net-(J2-Pad2)") (class "Default")
      (node (ref "J2") (pin "2") (pinfunction "2_2") (pintype "passive"))
      (node (ref "R58") (pin "1") (pinfunction "1_1") (pintype "passive"))
    )
    (net (code "35") (name "Net-(J2-Pad3)") (class "Default")
      (node (ref "J2") (pin "3") (pinfunction "3_3") (pintype "passive"))
      (node (ref "R23") (pin "1") (pinfunction "1_1") (pintype "passive"))
    )
    (net (code "36") (name "Net-(LED1-Pad2)") (class "Default")
      (node (ref "LED1") (pin "2") (pinfunction "2_2") (pintype "passive"))
      (node (ref "LED1") (pin "4") (pinfunction "4_4") (pintype "passive"))
      (node (ref "R11") (pin "1") (pinfunction "1_1") (pintype "passive"))
    )
    (net (code "37") (name "Net-(LED2-Pad2)") (class "Default")
      (node (ref "LED2") (pin "2") (pinfunction "2_2") (pintype "passive"))
      (node (ref "LED2") (pin "4") (pinfunction "4_4") (pintype "passive"))
      (node (ref "R12") (pin "1") (pinfunction "1_1") (pintype "passive"))
    )
    (net (code "38") (name "Net-(LED3-Pad2)") (class "Default")
      (node (ref "LED3") (pin "2") (pinfunction "2_2") (pintype "passive"))
      (node (ref "LED3") (pin "4") (pinfunction "4_4") (pintype "passive"))
      (node (ref "R13") (pin "1") (pinfunction "1_1") (pintype "passive"))
    )
    (net (code "39") (name "Net-(LED4-Pad2)") (class "Default")
      (node (ref "LED4") (pin "2") (pinfunction "2_2") (pintype "passive"))
      (node (ref "LED4") (pin "4") (pinfunction "4_4") (pintype "passive"))
      (node (ref "R8") (pin "1") (pinfunction "1_1") (pintype "passive"))
    )
    (net (code "40") (name "Net-(LED5-Pad2)") (class "Default")
      (node (ref "LED5") (pin "2") (pinfunction "2_2") (pintype "passive"))
      (node (ref "LED5") (pin "4") (pinfunction "4_4") (pintype "passive"))
      (node (ref "R17") (pin "1") (pinfunction "1_1") (pintype "passive"))
    )
    (net (code "41") (name "Net-(LED6-Pad2)") (class "Default")
      (node (ref "LED6") (pin "2") (pinfunction "2_2") (pintype "passive"))
      (node (ref "LED6") (pin "4") (pinfunction "4_4") (pintype "passive"))
      (node (ref "R22") (pin "1") (pinfunction "1_1") (pintype "passive"))
    )
    (net (code "42") (name "Net-(LED7-Pad2)") (class "Default")
      (node (ref "LED7") (pin "2") (pinfunction "2_2") (pintype "passive"))
      (node (ref "LED7") (pin "4") (pinfunction "4_4") (pintype "passive"))
      (node (ref "R14") (pin "2") (pinfunction "2_2") (pintype "passive"))
    )
    (net (code "43") (name "Net-(LED8-Pad2)") (class "Default")
      (node (ref "LED8") (pin "2") (pinfunction "2_2") (pintype "passive"))
      (node (ref "LED8") (pin "4") (pinfunction "4_4") (pintype "passive"))
      (node (ref "R16") (pin "2") (pinfunction "2_2") (pintype "passive"))
    )
    (net (code "44") (name "Net-(LED9-Pad2)") (class "Default")
      (node (ref "LED9") (pin "2") (pinfunction "2_2") (pintype "passive"))
      (node (ref "LED9") (pin "4") (pinfunction "4_4") (pintype "passive"))
      (node (ref "R24") (pin "2") (pinfunction "2_2") (pintype "passive"))
    )
    (net (code "45") (name "Net-(LED10-Pad2)") (class "Default")
      (node (ref "LED10") (pin "2") (pinfunction "2_2") (pintype "passive"))
      (node (ref "LED10") (pin "4") (pinfunction "4_4") (pintype "passive"))
      (node (ref "R27") (pin "2") (pinfunction "2_2") (pintype "passive"))
    )
    (net (code "46") (name "Net-(LED11-Pad2)") (class "Default")
      (node (ref "LED11") (pin "2") (pinfunction "2_2") (pintype "passive"))
      (node (ref "LED11") (pin "4") (pinfunction "4_4") (pintype "passive"))
      (node (ref "R28") (pin "2") (pinfunction "2_2") (pintype "passive"))
    )
    (net (code "47") (name "Net-(LED12-Pad2)") (class "Default")
      (node (ref "LED12") (pin "2") (pinfunction "2_2") (pintype "passive"))
      (node (ref "LED12") (pin "4") (pinfunction "4_4") (pintype "passive"))
      (node (ref "R33") (pin "2") (pinfunction "2_2") (pintype "passive"))
    )
    (net (code "48") (name "Net-(Q1-D)") (class "Default")
      (node (ref "B1") (pin "1") (pinfunction "1_1") (pintype "passive"))
      (node (ref "Q1") (pin "3") (pinfunction "D_3") (pintype "passive"))
      (node (ref "R2") (pin "1") (pinfunction "1_1") (pintype "passive"))
      (node (ref "R4") (pin "2") (pinfunction "2_2") (pintype "passive"))
    )
    (net (code "49") (name "Net-(Q2-D)") (class "Default")
      (node (ref "B2") (pin "1") (pinfunction "1_1") (pintype "passive"))
      (node (ref "Q2") (pin "3") (pinfunction "D_3") (pintype "passive"))
      (node (ref "R10") (pin "2") (pinfunction "2_2") (pintype "passive"))
      (node (ref "R57") (pin "1") (pinfunction "1_1") (pintype "passive"))
    )
    (net (code "50") (name "Net-(Q4-D)") (class "Default")
      (node (ref "B3") (pin "1") (pinfunction "1_1") (pintype "passive"))
      (node (ref "Q4") (pin "3") (pinfunction "D_3") (pintype "passive"))
      (node (ref "R18") (pin "1") (pinfunction "1_1") (pintype "passive"))
      (node (ref "R20") (pin "2") (pinfunction "2_2") (pintype "passive"))
    )
    (net (code "51") (name "Net-(Q5-D)") (class "Default")
      (node (ref "B8") (pin "1") (pinfunction "1_1") (pintype "passive"))
      (node (ref "Q5") (pin "3") (pinfunction "D_3") (pintype "passive"))
      (node (ref "R19") (pin "1") (pinfunction "1_1") (pintype "passive"))
      (node (ref "R21") (pin "2") (pinfunction "2_2") (pintype "passive"))
    )
    (net (code "52") (name "Net-(Q6-D)") (class "Default")
      (node (ref "B4") (pin "1") (pinfunction "1_1") (pintype "passive"))
      (node (ref "Q6") (pin "3") (pinfunction "D_3") (pintype "passive"))
      (node (ref "R29") (pin "1") (pinfunction "1_1") (pintype "passive"))
      (node (ref "R31") (pin "2") (pinfunction "2_2") (pintype "passive"))
    )
    (net (code "53") (name "Net-(Q7-D)") (class "Default")
      (node (ref "B7") (pin "1") (pinfunction "1_1") (pintype "passive"))
      (node (ref "Q7") (pin "3") (pinfunction "D_3") (pintype "passive"))
      (node (ref "R30") (pin "1") (pinfunction "1_1") (pintype "passive"))
      (node (ref "R32") (pin "2") (pinfunction "2_2") (pintype "passive"))
    )
    (net (code "54") (name "Net-(Q9-D)") (class "Default")
      (node (ref "B6") (pin "1") (pinfunction "1_1") (pintype "passive"))
      (node (ref "Q9") (pin "3") (pinfunction "D_3") (pintype "passive"))
      (node (ref "R40") (pin "1") (pinfunction "1_1") (pintype "passive"))
      (node (ref "R41") (pin "2") (pinfunction "2_2") (pintype "passive"))
    )
    (net (code "55") (name "Net-(Q10-D)") (class "Default")
      (node (ref "B5") (pin "1") (pinfunction "1_1") (pintype "passive"))
      (node (ref "Q10") (pin "3") (pinfunction "D_3") (pintype "passive"))
      (node (ref "R45") (pin "1") (pinfunction "1_1") (pintype "passive"))
      (node (ref "R46") (pin "2") (pinfunction "2_2") (pintype "passive"))
    )
    (net (code "56") (name "Net-(Q13-D)") (class "Default")
      (node (ref "B9") (pin "1") (pinfunction "1_1") (pintype "passive"))
      (node (ref "Q13") (pin "3") (pinfunction "D_3") (pintype "passive"))
      (node (ref "R37") (pin "2") (pinfunction "2_2") (pintype "passive"))
      (node (ref "R9") (pin "1") (pinfunction "1_1") (pintype "passive"))
    )
    (net (code "57") (name "Net-(Q14-D)") (class "Default")
      (node (ref "B10") (pin "1") (pinfunction "1_1") (pintype "passive"))
      (node (ref "Q14") (pin "3") (pinfunction "D_3") (pintype "passive"))
      (node (ref "R36") (pin "1") (pinfunction "1_1") (pintype "passive"))
      (node (ref "R39") (pin "2") (pinfunction "2_2") (pintype "passive"))
    )
    (net (code "58") (name "Net-(Q15-D)") (class "Default")
      (node (ref "B11") (pin "1") (pinfunction "1_1") (pintype "passive"))
      (node (ref "Q15") (pin "3") (pinfunction "D_3") (pintype "passive"))
      (node (ref "R50") (pin "1") (pinfunction "1_1") (pintype "passive"))
      (node (ref "R52") (pin "2") (pinfunction "2_2") (pintype "passive"))
    )
    (net (code "59") (name "Net-(Q16-D)") (class "Default")
      (node (ref "B12") (pin "1") (pinfunction "1_1") (pintype "passive"))
      (node (ref "Q16") (pin "3") (pinfunction "D_3") (pintype "passive"))
      (node (ref "R51") (pin "1") (pinfunction "1_1") (pintype "passive"))
      (node (ref "R53") (pin "2") (pinfunction "2_2") (pintype "passive"))
    )
    (net (code "60") (name "Net-(Q17-G)") (class "Default")
      (node (ref "Q17") (pin "4") (pinfunction "G_4") (pintype "passive"))
      (node (ref "Q19") (pin "3") (pinfunction "C_3") (pintype "passive"))
      (node (ref "R56") (pin "1") (pinfunction "1_1") (pintype "passive"))
    )
    (net (code "61") (name "Net-(Q19-B)") (class "Default")
      (node (ref "Q19") (pin "1") (pinfunction "B_1") (pintype "passive"))
      (node (ref "R35") (pin "2") (pinfunction "2_2") (pintype "passive"))
      (node (ref "R5") (pin "2") (pinfunction "2_2") (pintype "passive"))
    )
    (net (code "62") (name "Net-(U1-VDD)") (class "Default")
      (node (ref "C12") (pin "2") (pinfunction "2_2") (pintype "passive"))
      (node (ref "C6") (pin "2") (pinfunction "2_2") (pintype "passive"))
      (node (ref "R48") (pin "1") (pinfunction "1_1") (pintype "passive"))
      (node (ref "R49") (pin "1") (pinfunction "1_1") (pintype "passive"))
      (node (ref "U1") (pin "1") (pinfunction "VDD_1") (pintype "passive"))
    )
    (net (code "63") (name "VCC") (class "Default")
      (node (ref "J1") (pin "1") (pinfunction "V_1") (pintype "passive"))
      (node (ref "Q11") (pin "2") (pinfunction "S_2") (pintype "passive"))
      (node (ref "Q17") (pin "1") (pinfunction "S_1") (pintype "passive"))
      (node (ref "Q17") (pin "2") (pinfunction "S_2") (pintype "passive"))
      (node (ref "Q17") (pin "3") (pinfunction "S_3") (pintype "passive"))
      (node (ref "Q3") (pin "1") (pinfunction "S_1") (pintype "passive"))
      (node (ref "Q3") (pin "2") (pinfunction "S_2") (pintype "passive"))
      (node (ref "Q3") (pin "3") (pinfunction "S_3") (pintype "passive"))
      (node (ref "Q8") (pin "2") (pinfunction "S_2") (pintype "passive"))
      (node (ref "R1") (pin "2") (pinfunction "2_2") (pintype "passive"))
      (node (ref "R18") (pin "2") (pinfunction "2_2") (pintype "passive"))
      (node (ref "R19") (pin "2") (pinfunction "2_2") (pintype "passive"))
      (node (ref "R2") (pin "2") (pinfunction "2_2") (pintype "passive"))
      (node (ref "R29") (pin "2") (pinfunction "2_2") (pintype "passive"))
      (node (ref "R3") (pin "1") (pinfunction "1_1") (pintype "passive"))
      (node (ref "R30") (pin "2") (pinfunction "2_2") (pintype "passive"))
      (node (ref "R36") (pin "2") (pinfunction "2_2") (pintype "passive"))
      (node (ref "R40") (pin "2") (pinfunction "2_2") (pintype "passive"))
      (node (ref "R45") (pin "2") (pinfunction "2_2") (pintype "passive"))
      (node (ref "R49") (pin "2") (pinfunction "2_2") (pintype "passive"))
      (node (ref "R50") (pin "2") (pinfunction "2_2") (pintype "passive"))
      (node (ref "R51") (pin "2") (pinfunction "2_2") (pintype "passive"))
      (node (ref "R56") (pin "2") (pinfunction "2_2") (pintype "passive"))
      (node (ref "R57") (pin "2") (pinfunction "2_2") (pintype "passive"))
      (node (ref "R6") (pin "2") (pinfunction "2_2") (pintype "passive"))
      (node (ref "R61") (pin "1") (pinfunction "1_1") (pintype "passive"))
      (node (ref "R9") (pin "2") (pinfunction "2_2") (pintype "passive"))
    )
    (net (code "64") (name "VCC1") (class "Default")
      (node (ref "C1") (pin "2") (pinfunction "2_2") (pintype "passive"))
      (node (ref "C2") (pin "2") (pinfunction "2_2") (pintype "passive"))
      (node (ref "Q1") (pin "2") (pinfunction "S_2") (pintype "passive"))
      (node (ref "Q10") (pin "2") (pinfunction "S_2") (pintype "passive"))
      (node (ref "Q13") (pin "2") (pinfunction "S_2") (pintype "passive"))
      (node (ref "Q14") (pin "2") (pinfunction "S_2") (pintype "passive"))
      (node (ref "Q15") (pin "2") (pinfunction "S_2") (pintype "passive"))
      (node (ref "Q16") (pin "2") (pinfunction "S_2") (pintype "passive"))
      (node (ref "Q2") (pin "2") (pinfunction "S_2") (pintype "passive"))
      (node (ref "Q3") (pin "5") (pinfunction "D_5") (pintype "passive"))
      (node (ref "Q3") (pin "6") (pinfunction "D_6") (pintype "passive"))
      (node (ref "Q3") (pin "7") (pinfunction "D_7") (pintype "passive"))
      (node (ref "Q3") (pin "8") (pinfunction "D_8") (pintype "passive"))
      (node (ref "Q4") (pin "2") (pinfunction "S_2") (pintype "passive"))
      (node (ref "Q5") (pin "2") (pinfunction "S_2") (pintype "passive"))
      (node (ref "Q6") (pin "2") (pinfunction "S_2") (pintype "passive"))
      (node (ref "Q7") (pin "2") (pinfunction "S_2") (pintype "passive"))
      (node (ref "Q9") (pin "2") (pinfunction "S_2") (pintype "passive"))
      (node (ref "R1") (pin "1") (pinfunction "1_1") (pintype "passive"))
      (node (ref "R62") (pin "1") (pinfunction "1_1") (pintype "passive"))
      (node (ref "R63") (pin "1") (pinfunction "1_1") (pintype "passive"))
      (node (ref "R64") (pin "1") (pinfunction "1_1") (pintype "passive"))
      (node (ref "R65") (pin "1") (pinfunction "1_1") (pintype "passive"))
      (node (ref "R66") (pin "1") (pinfunction "1_1") (pintype "passive"))
      (node (ref "R67") (pin "1") (pinfunction "1_1") (pintype "passive"))
      (node (ref "R68") (pin "1") (pinfunction "1_1") (pintype "passive"))
      (node (ref "R69") (pin "1") (pinfunction "1_1") (pintype "passive"))
      (node (ref "R70") (pin "1") (pinfunction "1_1") (pintype "passive"))
      (node (ref "R71") (pin "1") (pinfunction "1_1") (pintype "passive"))
      (node (ref "R72") (pin "1") (pinfunction "1_1") (pintype "passive"))
      (node (ref "R73") (pin "1") (pinfunction "1_1") (pintype "passive"))
    )
    (net (code "65") (name "VIN") (class "Default")
      (node (ref "C3") (pin "2") (pinfunction "2_2") (pintype "passive"))
      (node (ref "C5") (pin "2") (pinfunction "2_2") (pintype "passive"))
      (node (ref "J2") (pin "4") (pinfunction "4_4") (pintype "passive"))
      (node (ref "Q17") (pin "5") (pinfunction "D_5") (pintype "passive"))
      (node (ref "Q17") (pin "6") (pinfunction "D_6") (pintype "passive"))
      (node (ref "Q17") (pin "7") (pinfunction "D_7") (pintype "passive"))
      (node (ref "Q17") (pin "8") (pinfunction "D_8") (pintype "passive"))
      (node (ref "R5") (pin "1") (pinfunction "1_1") (pintype "passive"))
    )
  )
)
